# untitled.net
KiCad netlist of a schematic drawn in EAGLE
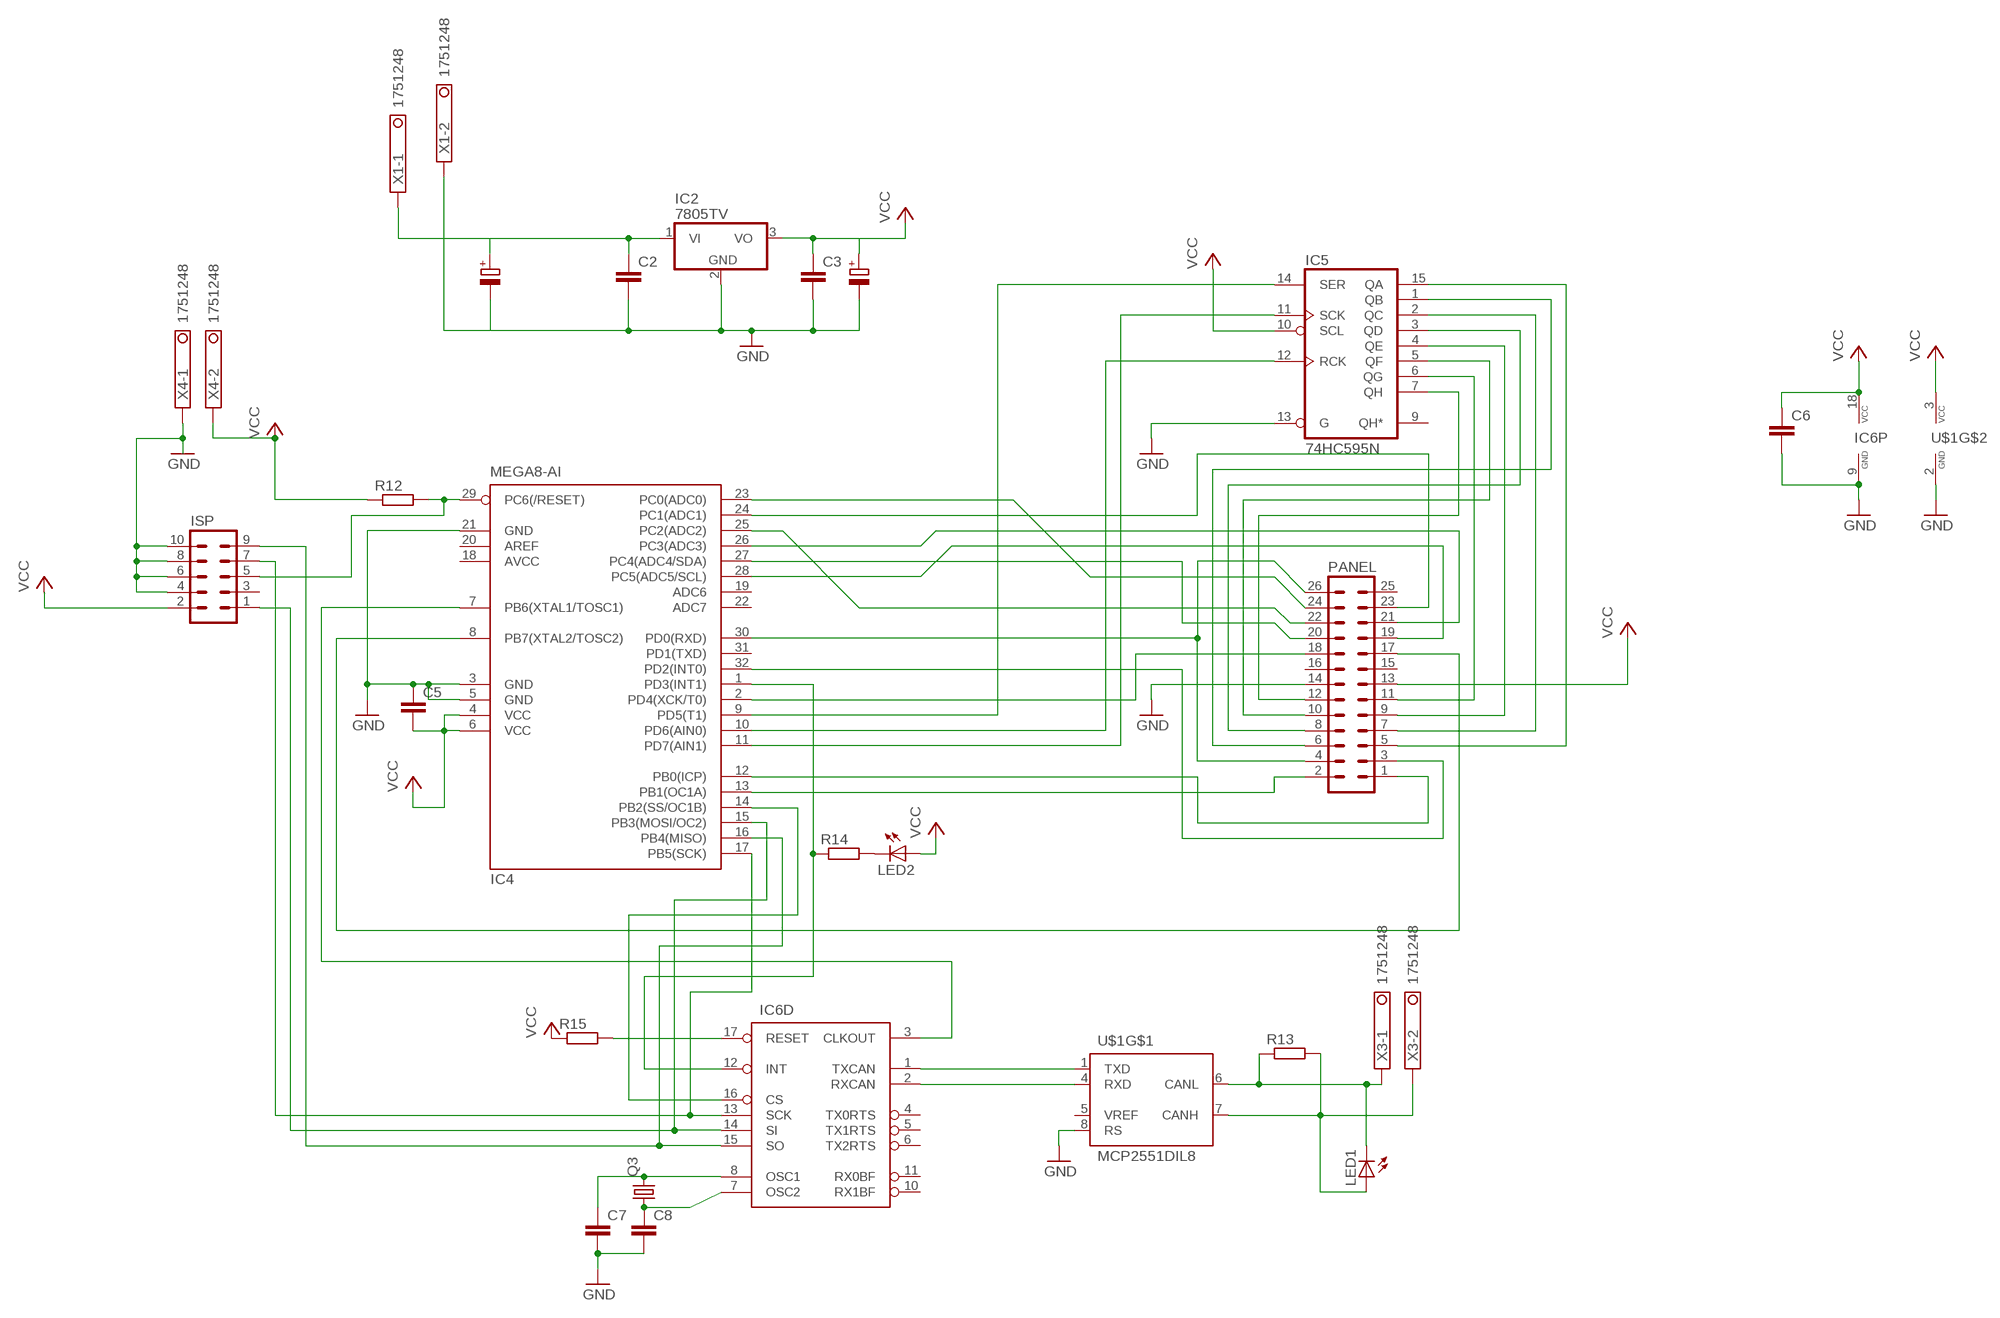
[diagram p0: schematic, sheet 1]

(export (version "E")
  (design (tool "Eeschema 10.0.6"))
  (components
    (comp (ref "C2")
      (value "C2.5/2")
      (footprint "eagle-import:C2.5-2")
      (libsource (lib "eagle-import") (part "C2.5/2"))
    )
    (comp (ref "C3")
      (value "C2.5/2")
      (footprint "eagle-import:C2.5-2")
      (libsource (lib "eagle-import") (part "C2.5/2"))
    )
    (comp (ref "C5")
      (value "C2.5/2")
      (footprint "eagle-import:C2.5-2")
      (libsource (lib "eagle-import") (part "C2.5/2"))
    )
    (comp (ref "C6")
      (value "C2.5/2")
      (footprint "eagle-import:C2.5-2")
      (libsource (lib "eagle-import") (part "C2.5/2"))
    )
    (comp (ref "C7")
      (value "C2.5/2")
      (footprint "eagle-import:C2.5-2")
      (libsource (lib "eagle-import") (part "C2.5/2"))
    )
    (comp (ref "C8")
      (value "C2.5/2")
      (footprint "eagle-import:C2.5-2")
      (libsource (lib "eagle-import") (part "C2.5/2"))
    )
    (comp (ref "IC2")
      (value "7805TV")
      (footprint "eagle-import:TO220V")
      (libsource (lib "eagle-import") (part "78TV05"))
    )
    (comp (ref "IC4")
      (value "MEGA8-AI")
      (footprint "eagle-import:TQFP32-08")
      (fields (field (name "MPN") "ATMEGA8-16AU"))
      (libsource (lib "eagle-import") (part "MEGA8-AI"))
    )
    (comp (ref "IC5")
      (value "74HC595N")
      (footprint "eagle-import:DIL16")
      (libsource (lib "eagle-import") (part "74595NHC"))
    )
    (comp (ref "IC6")
      (value "MCP2515P")
      (footprint "eagle-import:DIL18")
      (libsource (lib "eagle-import") (part "MCP2515P"))
    )
    (comp (ref "ISP")
      (value "ML10")
      (footprint "eagle-import:ML10")
      (libsource (lib "eagle-import") (part "ML10"))
    )
    (comp (ref "LED1")
      (value "LED3MM")
      (footprint "eagle-import:LED3MM")
      (libsource (lib "eagle-import") (part "LED3MM"))
    )
    (comp (ref "LED2")
      (value "LED3MM")
      (footprint "eagle-import:LED3MM")
      (libsource (lib "eagle-import") (part "LED3MM"))
    )
    (comp (ref "PANEL")
      (value "ML26")
      (footprint "eagle-import:ML26")
      (libsource (lib "eagle-import") (part "ML26"))
    )
    (comp (ref "Q3")
      (value "CRYSTALHC49U-V")
      (footprint "eagle-import:HC49U-V")
      (libsource (lib "eagle-import") (part "CRYSTALHC49U-V"))
    )
    (comp (ref "R12")
      (value "R-EU_0207/10")
      (footprint "eagle-import:0207_10")
      (libsource (lib "eagle-import") (part "R-EU_0207/10"))
    )
    (comp (ref "R13")
      (value "R-EU_0207/10")
      (footprint "eagle-import:0207_10")
      (libsource (lib "eagle-import") (part "R-EU_0207/10"))
    )
    (comp (ref "R14")
      (value "R-EU_0207/10")
      (footprint "eagle-import:0207_10")
      (libsource (lib "eagle-import") (part "R-EU_0207/10"))
    )
    (comp (ref "R15")
      (value "R-EU_0207/10")
      (footprint "eagle-import:0207_10")
      (libsource (lib "eagle-import") (part "R-EU_0207/10"))
    )
    (comp (ref "U$1")
      (value "MCP2551DIL8")
      (footprint "eagle-import:DIL08")
      (libsource (lib "eagle-import") (part "MCP2551DIL8"))
    )
    (comp (ref "X1")
      (value "1751248")
      (footprint "eagle-import:1751248")
      (libsource (lib "eagle-import") (part "1751248"))
    )
    (comp (ref "X3")
      (value "1751248")
      (footprint "eagle-import:1751248")
      (libsource (lib "eagle-import") (part "1751248"))
    )
    (comp (ref "X4")
      (value "1751248")
      (footprint "eagle-import:1751248")
      (libsource (lib "eagle-import") (part "1751248"))
    )
  )
  (nets
    (net (code "1") (name "/AVCC") (class "Default")
      (node (ref "IC4") (pin "18") (pinfunction "AVCC_18") (pintype "power_in"))
    )
    (net (code "2") (name "GND") (class "Default")
      (node (ref "C2") (pin "2") (pinfunction "2_2") (pintype "passive"))
      (node (ref "C3") (pin "2") (pinfunction "2_2") (pintype "passive"))
      (node (ref "C5") (pin "1") (pinfunction "1_1") (pintype "passive"))
      (node (ref "C6") (pin "2") (pinfunction "2_2") (pintype "passive"))
      (node (ref "C7") (pin "2") (pinfunction "2_2") (pintype "passive"))
      (node (ref "C8") (pin "2") (pinfunction "2_2") (pintype "passive"))
      (node (ref "IC2") (pin "2") (pinfunction "GND_2") (pintype "passive"))
      (node (ref "IC4") (pin "21") (pinfunction "GND_21") (pintype "power_in"))
      (node (ref "IC4") (pin "3") (pinfunction "GND_3") (pintype "power_in"))
      (node (ref "IC4") (pin "5") (pinfunction "GND_5") (pintype "power_in"))
      (node (ref "IC5") (pin "13") (pinfunction "G_13") (pintype "input"))
      (node (ref "IC6") (pin "9") (pinfunction "GND_9") (pintype "power_in"))
      (node (ref "ISP") (pin "10") (pinfunction "10_10") (pintype "passive"))
      (node (ref "ISP") (pin "4") (pinfunction "4_4") (pintype "passive"))
      (node (ref "ISP") (pin "6") (pinfunction "6_6") (pintype "passive"))
      (node (ref "ISP") (pin "8") (pinfunction "8_8") (pintype "passive"))
      (node (ref "PANEL") (pin "14") (pinfunction "14_14") (pintype "passive"))
      (node (ref "U$1") (pin "2") (pinfunction "GND_2") (pintype "power_in"))
      (node (ref "U$1") (pin "8") (pinfunction "RS_8") (pintype "bidirectional"))
      (node (ref "X1") (pin "2") (pinfunction "K_2") (pintype "passive"))
      (node (ref "X4") (pin "1") (pinfunction "K_1") (pintype "passive"))
    )
    (net (code "3") (name "Net-(IC2-VI)") (class "Default")
      (node (ref "C2") (pin "1") (pinfunction "1_1") (pintype "passive"))
      (node (ref "IC2") (pin "1") (pinfunction "VI_1") (pintype "input"))
      (node (ref "X1") (pin "1") (pinfunction "K_1") (pintype "passive"))
    )
    (net (code "4") (name "Net-(IC4-PB0(ICP))") (class "Default")
      (node (ref "IC4") (pin "12") (pinfunction "PB0(ICP)_12") (pintype "bidirectional"))
      (node (ref "PANEL") (pin "1") (pinfunction "1_1") (pintype "passive"))
    )
    (net (code "5") (name "Net-(IC4-PB1(OC1A))") (class "Default")
      (node (ref "IC4") (pin "13") (pinfunction "PB1(OC1A)_13") (pintype "bidirectional"))
      (node (ref "PANEL") (pin "2") (pinfunction "2_2") (pintype "passive"))
    )
    (net (code "6") (name "Net-(IC4-PB2(SS{slash}OC1B))") (class "Default")
      (node (ref "IC4") (pin "14") (pinfunction "PB2(SS/OC1B)_14") (pintype "bidirectional"))
      (node (ref "IC6") (pin "16") (pinfunction "CS_16") (pintype "input"))
    )
    (net (code "7") (name "Net-(IC4-PB3(MOSI{slash}OC2))") (class "Default")
      (node (ref "IC4") (pin "15") (pinfunction "PB3(MOSI/OC2)_15") (pintype "bidirectional"))
      (node (ref "IC6") (pin "14") (pinfunction "SI_14") (pintype "input"))
      (node (ref "ISP") (pin "1") (pinfunction "1_1") (pintype "passive"))
    )
    (net (code "8") (name "Net-(IC4-PB4(MISO))") (class "Default")
      (node (ref "IC4") (pin "16") (pinfunction "PB4(MISO)_16") (pintype "bidirectional"))
      (node (ref "IC6") (pin "15") (pinfunction "SO_15") (pintype "output"))
      (node (ref "ISP") (pin "9") (pinfunction "9_9") (pintype "passive"))
    )
    (net (code "9") (name "Net-(IC4-PB5(SCK))") (class "Default")
      (node (ref "IC4") (pin "17") (pinfunction "PB5(SCK)_17") (pintype "bidirectional"))
      (node (ref "IC6") (pin "13") (pinfunction "SCK_13") (pintype "input"))
      (node (ref "ISP") (pin "7") (pinfunction "7_7") (pintype "passive"))
    )
    (net (code "10") (name "Net-(IC4-PB6(XTAL1{slash}TOSC1))") (class "Default")
      (node (ref "IC4") (pin "7") (pinfunction "PB6(XTAL1/TOSC1)_7") (pintype "bidirectional"))
      (node (ref "IC6") (pin "3") (pinfunction "CLKOUT_3") (pintype "output"))
    )
    (net (code "11") (name "Net-(IC4-PB7(XTAL2{slash}TOSC2))") (class "Default")
      (node (ref "IC4") (pin "8") (pinfunction "PB7(XTAL2/TOSC2)_8") (pintype "bidirectional"))
      (node (ref "PANEL") (pin "17") (pinfunction "17_17") (pintype "passive"))
    )
    (net (code "12") (name "Net-(IC4-PC0(ADC0))") (class "Default")
      (node (ref "IC4") (pin "23") (pinfunction "PC0(ADC0)_23") (pintype "bidirectional"))
      (node (ref "PANEL") (pin "24") (pinfunction "24_24") (pintype "passive"))
    )
    (net (code "13") (name "Net-(IC4-PC1(ADC1))") (class "Default")
      (node (ref "IC4") (pin "24") (pinfunction "PC1(ADC1)_24") (pintype "bidirectional"))
      (node (ref "PANEL") (pin "23") (pinfunction "23_23") (pintype "passive"))
    )
    (net (code "14") (name "Net-(IC4-PC2(ADC2))") (class "Default")
      (node (ref "IC4") (pin "25") (pinfunction "PC2(ADC2)_25") (pintype "bidirectional"))
      (node (ref "PANEL") (pin "22") (pinfunction "22_22") (pintype "passive"))
    )
    (net (code "15") (name "Net-(IC4-PC3(ADC3))") (class "Default")
      (node (ref "IC4") (pin "26") (pinfunction "PC3(ADC3)_26") (pintype "bidirectional"))
      (node (ref "PANEL") (pin "21") (pinfunction "21_21") (pintype "passive"))
    )
    (net (code "16") (name "Net-(IC4-PC4(ADC4{slash}SDA))") (class "Default")
      (node (ref "IC4") (pin "27") (pinfunction "PC4(ADC4/SDA)_27") (pintype "bidirectional"))
      (node (ref "PANEL") (pin "20") (pinfunction "20_20") (pintype "passive"))
    )
    (net (code "17") (name "Net-(IC4-PC5(ADC5{slash}SCL))") (class "Default")
      (node (ref "IC4") (pin "28") (pinfunction "PC5(ADC5/SCL)_28") (pintype "bidirectional"))
      (node (ref "PANEL") (pin "19") (pinfunction "19_19") (pintype "passive"))
    )
    (net (code "18") (name "Net-(IC4-PC6({slash}RESET))") (class "Default")
      (node (ref "IC4") (pin "29") (pinfunction "PC6(/RESET)_29") (pintype "bidirectional"))
      (node (ref "ISP") (pin "5") (pinfunction "5_5") (pintype "passive"))
      (node (ref "R12") (pin "2") (pinfunction "2_2") (pintype "passive"))
    )
    (net (code "19") (name "Net-(IC4-PD0(RXD))") (class "Default")
      (node (ref "IC4") (pin "30") (pinfunction "PD0(RXD)_30") (pintype "bidirectional"))
      (node (ref "PANEL") (pin "26") (pinfunction "26_26") (pintype "passive"))
      (node (ref "PANEL") (pin "4") (pinfunction "4_4") (pintype "passive"))
    )
    (net (code "20") (name "Net-(IC4-PD2(INT0))") (class "Default")
      (node (ref "IC4") (pin "32") (pinfunction "PD2(INT0)_32") (pintype "bidirectional"))
      (node (ref "PANEL") (pin "3") (pinfunction "3_3") (pintype "passive"))
    )
    (net (code "21") (name "Net-(IC4-PD3(INT1))") (class "Default")
      (node (ref "IC4") (pin "1") (pinfunction "PD3(INT1)_1") (pintype "bidirectional"))
      (node (ref "IC6") (pin "12") (pinfunction "INT_12") (pintype "output"))
      (node (ref "R14") (pin "1") (pinfunction "1_1") (pintype "passive"))
    )
    (net (code "22") (name "Net-(IC4-PD4(XCK{slash}T0))") (class "Default")
      (node (ref "IC4") (pin "2") (pinfunction "PD4(XCK/T0)_2") (pintype "bidirectional"))
      (node (ref "PANEL") (pin "18") (pinfunction "18_18") (pintype "passive"))
    )
    (net (code "23") (name "Net-(IC4-PD5(T1))") (class "Default")
      (node (ref "IC4") (pin "9") (pinfunction "PD5(T1)_9") (pintype "bidirectional"))
      (node (ref "IC5") (pin "14") (pinfunction "SER_14") (pintype "input"))
    )
    (net (code "24") (name "Net-(IC4-PD6(AIN0))") (class "Default")
      (node (ref "IC4") (pin "10") (pinfunction "PD6(AIN0)_10") (pintype "bidirectional"))
      (node (ref "IC5") (pin "12") (pinfunction "RCK_12") (pintype "input"))
    )
    (net (code "25") (name "Net-(IC4-PD7(AIN1))") (class "Default")
      (node (ref "IC4") (pin "11") (pinfunction "PD7(AIN1)_11") (pintype "bidirectional"))
      (node (ref "IC5") (pin "11") (pinfunction "SCK_11") (pintype "input"))
    )
    (net (code "26") (name "Net-(IC5A-QA)") (class "Default")
      (node (ref "IC5") (pin "15") (pinfunction "QA_15") (pintype "tri_state"))
      (node (ref "PANEL") (pin "5") (pinfunction "5_5") (pintype "passive"))
    )
    (net (code "27") (name "Net-(IC5A-QB)") (class "Default")
      (node (ref "IC5") (pin "1") (pinfunction "QB_1") (pintype "tri_state"))
      (node (ref "PANEL") (pin "6") (pinfunction "6_6") (pintype "passive"))
    )
    (net (code "28") (name "Net-(IC5A-QC)") (class "Default")
      (node (ref "IC5") (pin "2") (pinfunction "QC_2") (pintype "tri_state"))
      (node (ref "PANEL") (pin "7") (pinfunction "7_7") (pintype "passive"))
    )
    (net (code "29") (name "Net-(IC5A-QD)") (class "Default")
      (node (ref "IC5") (pin "3") (pinfunction "QD_3") (pintype "tri_state"))
      (node (ref "PANEL") (pin "8") (pinfunction "8_8") (pintype "passive"))
    )
    (net (code "30") (name "Net-(IC5A-QE)") (class "Default")
      (node (ref "IC5") (pin "4") (pinfunction "QE_4") (pintype "tri_state"))
      (node (ref "PANEL") (pin "9") (pinfunction "9_9") (pintype "passive"))
    )
    (net (code "31") (name "Net-(IC5A-QF)") (class "Default")
      (node (ref "IC5") (pin "5") (pinfunction "QF_5") (pintype "tri_state"))
      (node (ref "PANEL") (pin "10") (pinfunction "10_10") (pintype "passive"))
    )
    (net (code "32") (name "Net-(IC5A-QG)") (class "Default")
      (node (ref "IC5") (pin "6") (pinfunction "QG_6") (pintype "tri_state"))
      (node (ref "PANEL") (pin "11") (pinfunction "11_11") (pintype "passive"))
    )
    (net (code "33") (name "Net-(IC5A-QH)") (class "Default")
      (node (ref "IC5") (pin "7") (pinfunction "QH_7") (pintype "tri_state"))
      (node (ref "PANEL") (pin "12") (pinfunction "12_12") (pintype "passive"))
    )
    (net (code "34") (name "Net-(IC6A-OSC1)") (class "Default")
      (node (ref "C7") (pin "1") (pinfunction "1_1") (pintype "passive"))
      (node (ref "IC6") (pin "8") (pinfunction "OSC1_8") (pintype "input"))
      (node (ref "Q3") (pin "2") (pinfunction "2_2") (pintype "passive"))
    )
    (net (code "35") (name "Net-(IC6A-OSC2)") (class "Default")
      (node (ref "C8") (pin "1") (pinfunction "1_1") (pintype "passive"))
      (node (ref "IC6") (pin "7") (pinfunction "OSC2_7") (pintype "input"))
      (node (ref "Q3") (pin "1") (pinfunction "1_1") (pintype "passive"))
    )
    (net (code "36") (name "Net-(IC6A-RESET)") (class "Default")
      (node (ref "IC6") (pin "17") (pinfunction "RESET_17") (pintype "input"))
      (node (ref "R15") (pin "2") (pinfunction "2_2") (pintype "passive"))
    )
    (net (code "37") (name "Net-(IC6A-RXCAN)") (class "Default")
      (node (ref "IC6") (pin "2") (pinfunction "RXCAN_2") (pintype "input"))
      (node (ref "U$1") (pin "4") (pinfunction "RXD_4") (pintype "bidirectional"))
    )
    (net (code "38") (name "Net-(IC6A-TXCAN)") (class "Default")
      (node (ref "IC6") (pin "1") (pinfunction "TXCAN_1") (pintype "output"))
      (node (ref "U$1") (pin "1") (pinfunction "TXD_1") (pintype "bidirectional"))
    )
    (net (code "39") (name "Net-(LED1-C)") (class "Default")
      (node (ref "LED1") (pin "K") (pinfunction "C_K") (pintype "passive"))
      (node (ref "R13") (pin "1") (pinfunction "1_1") (pintype "passive"))
      (node (ref "U$1") (pin "6") (pinfunction "CANL_6") (pintype "bidirectional"))
      (node (ref "X3") (pin "1") (pinfunction "K_1") (pintype "passive"))
    )
    (net (code "40") (name "Net-(LED2-C)") (class "Default")
      (node (ref "LED2") (pin "K") (pinfunction "C_K") (pintype "passive"))
      (node (ref "R14") (pin "2") (pinfunction "2_2") (pintype "passive"))
    )
    (net (code "41") (name "Net-(U$1A-CANH)") (class "Default")
      (node (ref "LED1") (pin "A") (pinfunction "A_A") (pintype "passive"))
      (node (ref "R13") (pin "2") (pinfunction "2_2") (pintype "passive"))
      (node (ref "U$1") (pin "7") (pinfunction "CANH_7") (pintype "bidirectional"))
      (node (ref "X3") (pin "2") (pinfunction "K_2") (pintype "passive"))
    )
    (net (code "42") (name "VCC") (class "Default")
      (node (ref "C3") (pin "1") (pinfunction "1_1") (pintype "passive"))
      (node (ref "C5") (pin "2") (pinfunction "2_2") (pintype "passive"))
      (node (ref "C6") (pin "1") (pinfunction "1_1") (pintype "passive"))
      (node (ref "IC2") (pin "3") (pinfunction "VO_3") (pintype "passive"))
      (node (ref "IC4") (pin "4") (pinfunction "VCC_4") (pintype "power_in"))
      (node (ref "IC4") (pin "6") (pinfunction "VCC_6") (pintype "power_in"))
      (node (ref "IC5") (pin "10") (pinfunction "SCL_10") (pintype "input"))
      (node (ref "IC6") (pin "18") (pinfunction "VCC_18") (pintype "power_in"))
      (node (ref "ISP") (pin "2") (pinfunction "2_2") (pintype "passive"))
      (node (ref "LED2") (pin "A") (pinfunction "A_A") (pintype "passive"))
      (node (ref "PANEL") (pin "13") (pinfunction "13_13") (pintype "passive"))
      (node (ref "R12") (pin "1") (pinfunction "1_1") (pintype "passive"))
      (node (ref "R15") (pin "1") (pinfunction "1_1") (pintype "passive"))
      (node (ref "U$1") (pin "3") (pinfunction "VCC_3") (pintype "power_in"))
      (node (ref "X4") (pin "2") (pinfunction "K_2") (pintype "passive"))
    )
    (net (code "43") (name "unconnected-(IC4-ADC6-Pad19)") (class "Default")
      (node (ref "IC4") (pin "19") (pinfunction "ADC6_19") (pintype "bidirectional"))
    )
    (net (code "44") (name "unconnected-(IC4-ADC7-Pad22)") (class "Default")
      (node (ref "IC4") (pin "22") (pinfunction "ADC7_22") (pintype "bidirectional"))
    )
    (net (code "45") (name "unconnected-(IC4-AREF-Pad20)") (class "Default")
      (node (ref "IC4") (pin "20") (pinfunction "AREF_20") (pintype "passive"))
    )
    (net (code "46") (name "unconnected-(IC4-PD1(TXD)-Pad31)") (class "Default")
      (node (ref "IC4") (pin "31") (pinfunction "PD1(TXD)_31") (pintype "bidirectional"))
    )
    (net (code "47") (name "unconnected-(IC5A-QH*-Pad9)") (class "Default")
      (node (ref "IC5") (pin "9") (pinfunction "QH*_9") (pintype "tri_state"))
    )
    (net (code "48") (name "unconnected-(IC6A-RX0BF-Pad11)") (class "Default")
      (node (ref "IC6") (pin "11") (pinfunction "RX0BF_11") (pintype "output"))
    )
    (net (code "49") (name "unconnected-(IC6A-RX1BF-Pad10)") (class "Default")
      (node (ref "IC6") (pin "10") (pinfunction "RX1BF_10") (pintype "output"))
    )
    (net (code "50") (name "unconnected-(IC6A-TX0RTS-Pad4)") (class "Default")
      (node (ref "IC6") (pin "4") (pinfunction "TX0RTS_4") (pintype "input"))
    )
    (net (code "51") (name "unconnected-(IC6A-TX1RTS-Pad5)") (class "Default")
      (node (ref "IC6") (pin "5") (pinfunction "TX1RTS_5") (pintype "input"))
    )
    (net (code "52") (name "unconnected-(IC6A-TX2RTS-Pad6)") (class "Default")
      (node (ref "IC6") (pin "6") (pinfunction "TX2RTS_6") (pintype "input"))
    )
    (net (code "53") (name "unconnected-(ISP-Pad3)") (class "Default")
      (node (ref "ISP") (pin "3") (pinfunction "3_3") (pintype "passive"))
    )
    (net (code "54") (name "unconnected-(PANEL-Pad15)") (class "Default")
      (node (ref "PANEL") (pin "15") (pinfunction "15_15") (pintype "passive"))
    )
    (net (code "55") (name "unconnected-(PANEL-Pad16)") (class "Default")
      (node (ref "PANEL") (pin "16") (pinfunction "16_16") (pintype "passive"))
    )
    (net (code "56") (name "unconnected-(PANEL-Pad25)") (class "Default")
      (node (ref "PANEL") (pin "25") (pinfunction "25_25") (pintype "passive"))
    )
    (net (code "57") (name "unconnected-(U$1A-VREF-Pad5)") (class "Default")
      (node (ref "U$1") (pin "5") (pinfunction "VREF_5") (pintype "bidirectional"))
    )
  )
)
